# AIRZAI_NFC_READER_FLEX.net
KiCad netlist of a schematic drawn in Altium Designer
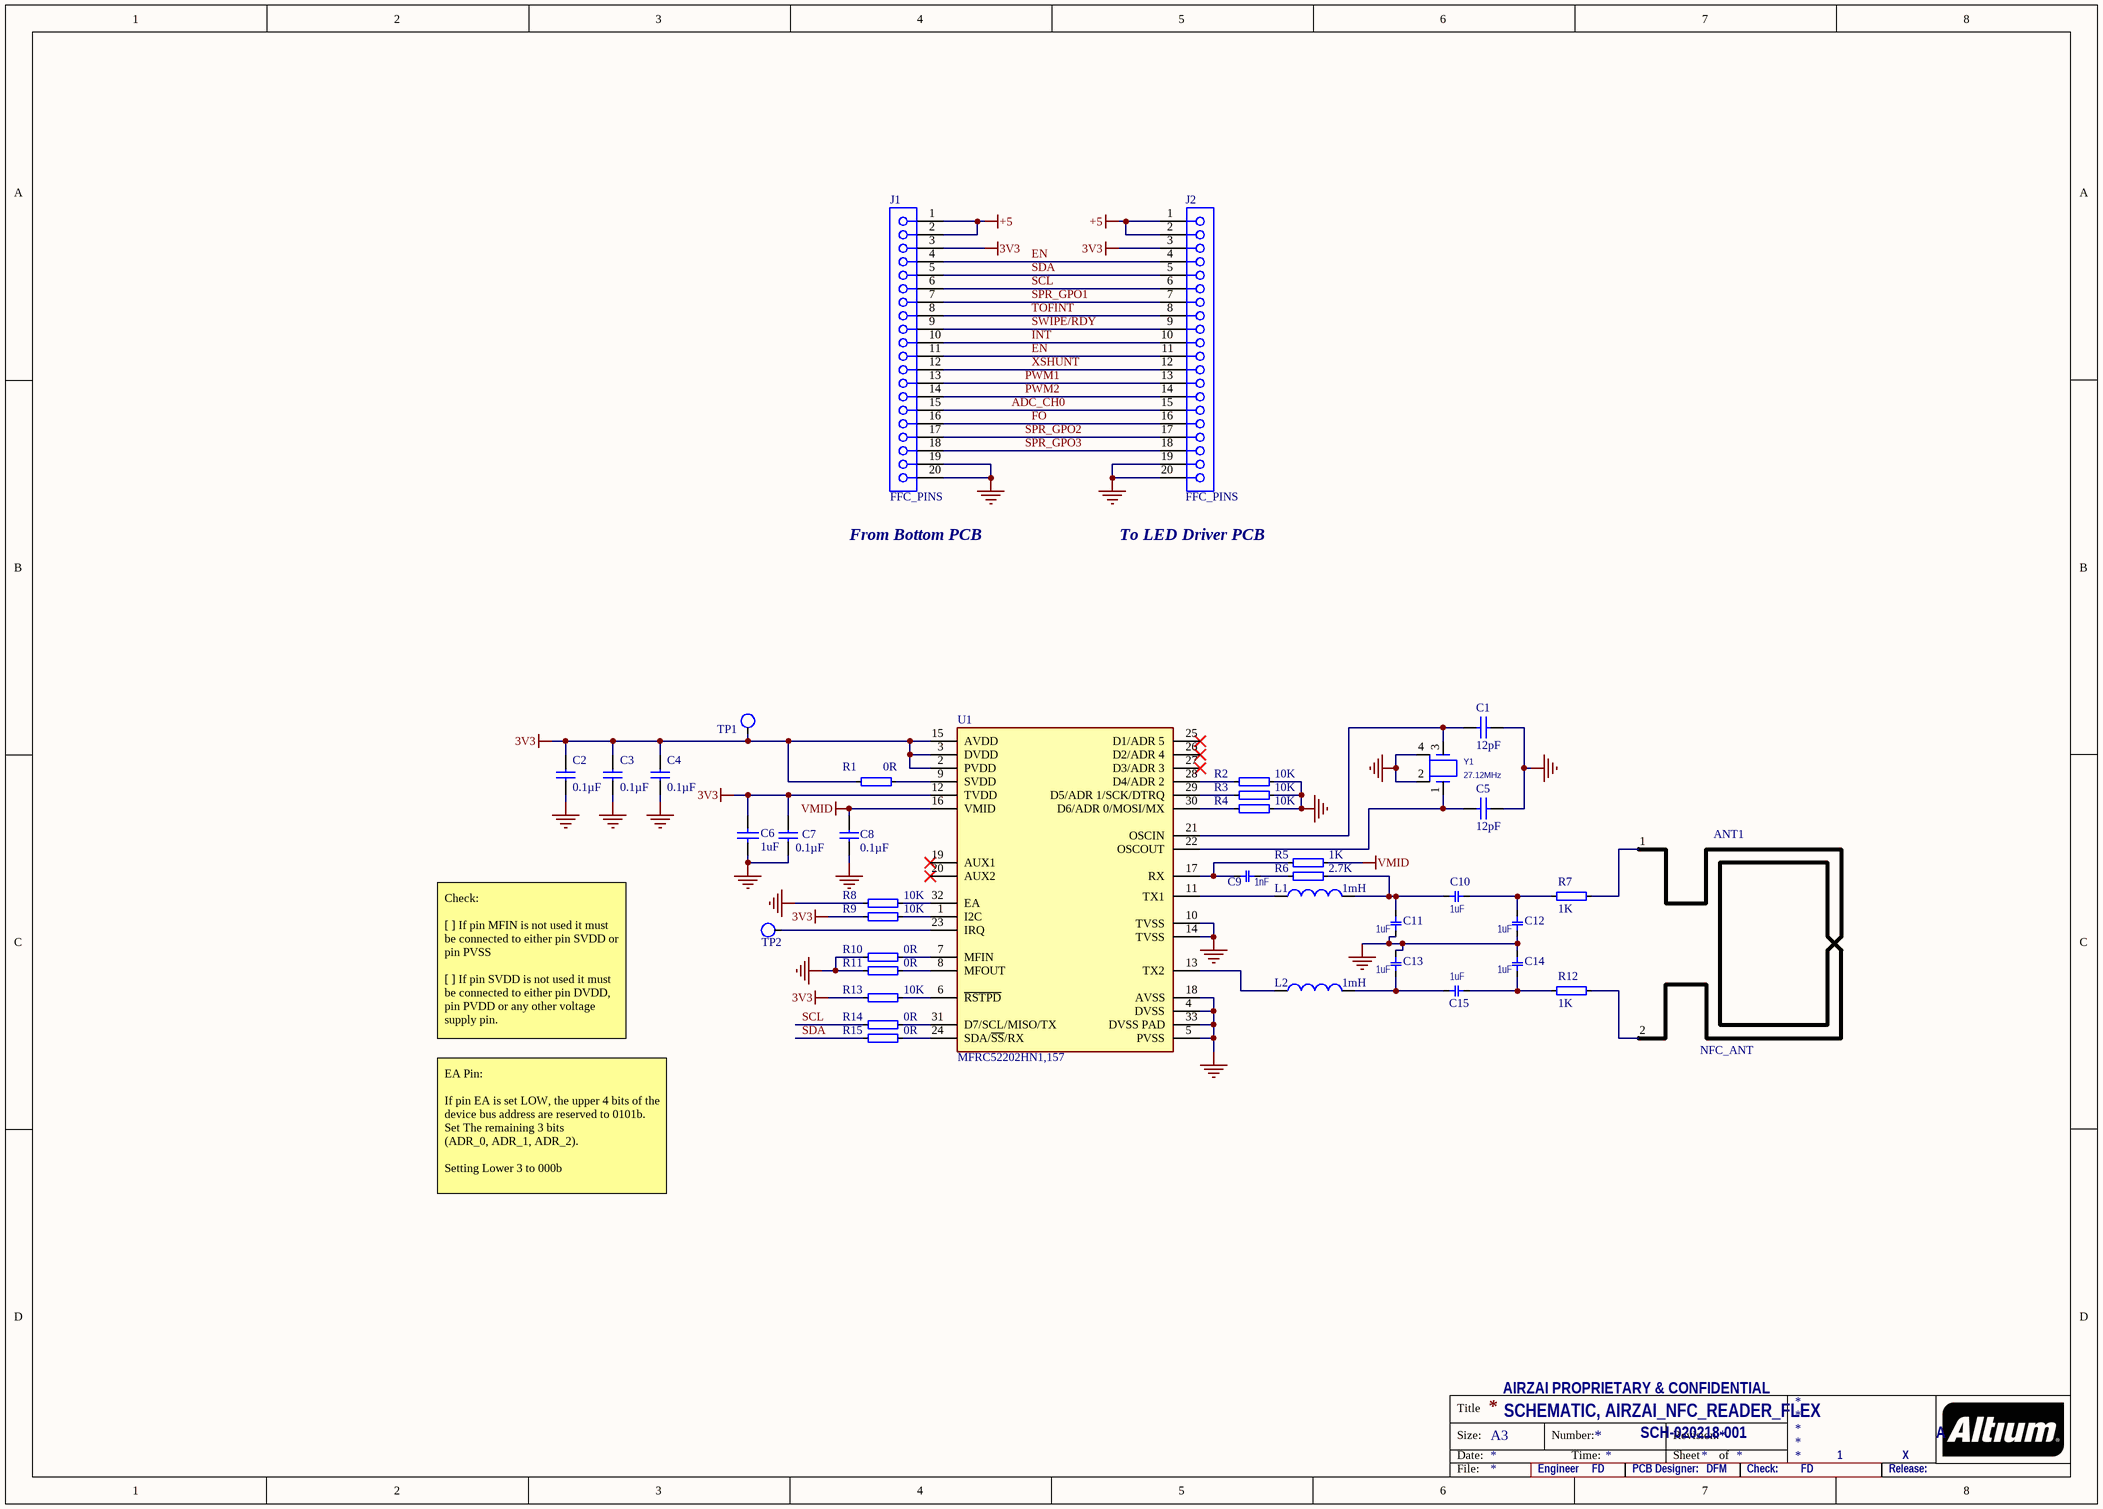
[diagram p0: AIRZAI_NFC_READER_FLEX.SchDoc]

(export (version "E")
  (design (tool "Eeschema 10.0.6"))
  (components
    (comp (ref "ANT1") (value "NFC_ANT") (libsource (lib "AIRZAI_LED_SENSE_FLEX_REVA") (part "NFC_ANT")))
    (comp (ref "C1")
      (value "12pF")
      (description "CAP CER 12PF 50V C0G/NP0 0402")
      (fields
        (field (name "MANUFACTURER") "KEMET")
        (field (name "MANUFACTURER PART NUMBER") "C0402C120J5GACTU")
      )
      (libsource (lib "AIRZAI_LED_SENSE_FLEX_REVA") (part "CAP"))
    )
    (comp (ref "C2")
      (value "0.1µF")
      (footprint "0402CAP")
      (description "Capacitor, X7R, ±10%")
      (fields (field (name "MANUFACTURER") "TDK") (field (name "MANUFACTURER PART NUMBER") "C1005X7R1C104K"))
      (libsource (lib "Nordic Passive DB") (part "CAP"))
    )
    (comp (ref "C3")
      (value "0.1µF")
      (footprint "0402CAP")
      (description "Capacitor, X7R, ±10%")
      (fields (field (name "MANUFACTURER") "TDK") (field (name "MANUFACTURER PART NUMBER") "C1005X7R1C104K"))
      (libsource (lib "Nordic Passive DB") (part "CAP"))
    )
    (comp (ref "C4")
      (value "0.1µF")
      (footprint "0402CAP")
      (description "Capacitor, X7R, ±10%")
      (fields (field (name "MANUFACTURER") "TDK") (field (name "MANUFACTURER PART NUMBER") "C1005X7R1C104K"))
      (libsource (lib "Nordic Passive DB") (part "CAP"))
    )
    (comp (ref "C5")
      (value "12pF")
      (description "CAP CER 12PF 50V C0G/NP0 0402")
      (fields
        (field (name "MANUFACTURER") "KEMET")
        (field (name "MANUFACTURER PART NUMBER") "C0402C120J5GACTU")
      )
      (libsource (lib "AIRZAI_LED_SENSE_FLEX_REVA") (part "CAP"))
    )
    (comp (ref "C6")
      (value "1uF")
      (footprint "CAPC0402(1005)60_M")
      (description "CAP 1uF 16V ±10% 0402 (1005 Metric) Thickness 0.6mm SMD")
      (fields
        (field (name "MANUFACTURER") "Taiyo Yuden")
        (field (name "MANUFACTURER PART NUMBER") "EMK105BJ105KV-F")
      )
      (libsource (lib "AIRZAI_LED_SENSE_FLEX_REVA") (part "CAP"))
    )
    (comp (ref "C7")
      (value "0.1µF")
      (footprint "0402CAP")
      (description "Capacitor, X7R, ±10%")
      (fields (field (name "MANUFACTURER") "TDK") (field (name "MANUFACTURER PART NUMBER") "C1005X7R1C104K"))
      (libsource (lib "Nordic Passive DB") (part "CAP"))
    )
    (comp (ref "C8")
      (value "0.1µF")
      (footprint "0402CAP")
      (description "Capacitor, X7R, ±10%")
      (fields (field (name "MANUFACTURER") "TDK") (field (name "MANUFACTURER PART NUMBER") "C1005X7R1C104K"))
      (libsource (lib "Nordic Passive DB") (part "CAP"))
    )
    (comp (ref "C9") (value "1nF") (footprint "0603") (libsource (lib "LID2131_PN7462AU V2") (part "56p")))
    (comp (ref "C10") (value "1uF") (footprint "0603") (libsource (lib "LID2131_PN7462AU V2") (part "56p")))
    (comp (ref "C11") (value "1uF") (footprint "0603") (libsource (lib "LID2131_PN7462AU V2") (part "56p")))
    (comp (ref "C12") (value "1uF") (footprint "0603") (libsource (lib "LID2131_PN7462AU V2") (part "56p")))
    (comp (ref "C13") (value "1uF") (footprint "0603") (libsource (lib "LID2131_PN7462AU V2") (part "56p")))
    (comp (ref "C14") (value "1uF") (footprint "0603") (libsource (lib "LID2131_PN7462AU V2") (part "56p")))
    (comp (ref "C15") (value "1uF") (footprint "0603") (libsource (lib "LID2131_PN7462AU V2") (part "56p")))
    (comp (ref "J1") (value "FFC_PINS") (libsource (lib "AIRZAI_LED_SENSE_FLEX_REVA") (part "FFC_PINS")))
    (comp (ref "J2") (value "FFC_PINS") (libsource (lib "AIRZAI_LED_SENSE_FLEX_REVA") (part "FFC_PINS")))
    (comp (ref "L1")
      (value "1mH")
      (footprint "0402-A")
      (description "Inductor")
      (libsource (lib "Miscellaneous Devices") (part "Inductor"))
    )
    (comp (ref "L2")
      (value "1mH")
      (footprint "0402-A")
      (description "Inductor")
      (libsource (lib "Miscellaneous Devices") (part "Inductor"))
    )
    (comp (ref "R1")
      (value "0R")
      (footprint "0402")
      (description "Resistor, ±1%, 0.063W")
      (fields
        (field (name "MANUFACTURER") "Panasonic")
        (field (name "MANUFACTURER PART NUMBER") "ERJ-2GE0R00X")
      )
      (libsource (lib "Nordic Passive DB") (part "RES_1"))
    )
    (comp (ref "R2")
      (value "10K")
      (footprint "0402")
      (description "Resistor 10K, ±1%, 0.063W")
      (fields
        (field (name "MANUFACTURER") "Vishay Dale")
        (field (name "MANUFACTURER PART NUMBER") "CRCW040210K0JNED")
      )
      (libsource (lib "Nordic Passive DB") (part "RES_1"))
    )
    (comp (ref "R3")
      (value "10K")
      (footprint "0402")
      (description "Resistor 10K, ±1%, 0.063W")
      (fields
        (field (name "MANUFACTURER") "Vishay Dale")
        (field (name "MANUFACTURER PART NUMBER") "CRCW040210K0JNED")
      )
      (libsource (lib "Nordic Passive DB") (part "RES_1"))
    )
    (comp (ref "R4")
      (value "10K")
      (footprint "0402")
      (description "Resistor 10K, ±1%, 0.063W")
      (fields
        (field (name "MANUFACTURER") "Vishay Dale")
        (field (name "MANUFACTURER PART NUMBER") "CRCW040210K0JNED")
      )
      (libsource (lib "Nordic Passive DB") (part "RES_1"))
    )
    (comp (ref "R5")
      (value "1K")
      (footprint "0402")
      (description "Resistor 1K, ±1%, 0.063W")
      (libsource (lib "Nordic Passive DB") (part "RES_1"))
    )
    (comp (ref "R6")
      (value "2.7K")
      (footprint "0402")
      (description "Resistor 2.7K, ±1%, 0.063W")
      (libsource (lib "Nordic Passive DB") (part "RES_1"))
    )
    (comp (ref "R7")
      (value "1K")
      (description "Resistor 1K, ±1%, 0.063W")
      (libsource (lib "Nordic Passive DB") (part "RES_1"))
    )
    (comp (ref "R8")
      (value "10K")
      (footprint "0402")
      (description "Resistor 10K, ±1%, 0.063W")
      (fields
        (field (name "MANUFACTURER") "Vishay Dale")
        (field (name "MANUFACTURER PART NUMBER") "CRCW040210K0JNED")
      )
      (libsource (lib "Nordic Passive DB") (part "RES_1"))
    )
    (comp (ref "R9")
      (value "10K")
      (footprint "0402")
      (description "Resistor 10K, ±1%, 0.063W")
      (fields
        (field (name "MANUFACTURER") "Vishay Dale")
        (field (name "MANUFACTURER PART NUMBER") "CRCW040210K0JNED")
      )
      (libsource (lib "Nordic Passive DB") (part "RES_1"))
    )
    (comp (ref "R10")
      (value "0R")
      (footprint "0402")
      (description "Resistor, ±1%, 0.063W")
      (fields
        (field (name "MANUFACTURER") "Panasonic")
        (field (name "MANUFACTURER PART NUMBER") "ERJ-2GE0R00X")
      )
      (libsource (lib "Nordic Passive DB") (part "RES_1"))
    )
    (comp (ref "R11")
      (value "0R")
      (footprint "0402")
      (description "Resistor, ±1%, 0.063W")
      (fields
        (field (name "MANUFACTURER") "Panasonic")
        (field (name "MANUFACTURER PART NUMBER") "ERJ-2GE0R00X")
      )
      (libsource (lib "Nordic Passive DB") (part "RES_1"))
    )
    (comp (ref "R12")
      (value "1K")
      (description "Resistor 1K, ±1%, 0.063W")
      (libsource (lib "Nordic Passive DB") (part "RES_1"))
    )
    (comp (ref "R13")
      (value "10K")
      (footprint "0402")
      (description "Resistor 10K, ±1%, 0.063W")
      (fields
        (field (name "MANUFACTURER") "Vishay Dale")
        (field (name "MANUFACTURER PART NUMBER") "CRCW040210K0JNED")
      )
      (libsource (lib "Nordic Passive DB") (part "RES_1"))
    )
    (comp (ref "R14")
      (value "0R")
      (footprint "0402")
      (description "Resistor, ±1%, 0.063W")
      (fields
        (field (name "MANUFACTURER") "Panasonic")
        (field (name "MANUFACTURER PART NUMBER") "ERJ-2GE0R00X")
      )
      (libsource (lib "Nordic Passive DB") (part "RES_1"))
    )
    (comp (ref "R15")
      (value "0R")
      (footprint "0402")
      (description "Resistor, ±1%, 0.063W")
      (fields
        (field (name "MANUFACTURER") "Panasonic")
        (field (name "MANUFACTURER PART NUMBER") "ERJ-2GE0R00X")
      )
      (libsource (lib "Nordic Passive DB") (part "RES_1"))
    )
    (comp (ref "TP1")
      (value "WIREPT")
      (footprint "TP_0.9MM")
      (libsource (lib "AIRZAI_MBD_REVB") (part "WIREPT"))
    )
    (comp (ref "TP2")
      (value "WIREPT")
      (footprint "TP_0.9MM")
      (libsource (lib "AIRZAI_MBD_REVB") (part "WIREPT"))
    )
    (comp (ref "U1")
      (value "MFRC52201HN1,157")
      (footprint "NXP_SOT617-1_0")
      (description "IC RFID READER 13.56MHZ 32HVQFN")
      (fields
        (field (name "MANUFACTURER") "NXP")
        (field (name "MOUSER PART NUMBER") "771-MFRC52202HN1157")
        (field (name "PART NUMBER") "MFRC52202HN1,157")
      )
      (libsource (lib "AIRZAI_LED_SENSE_FLEX_REVA") (part "MFRC52201HN1,157"))
    )
    (comp (ref "Y1")
      (value "27.12MHz")
      (footprint "XTAL_2016")
      (description "CRYSTAL 27.12MHZ 10PF SMD")
      (fields
        (field (name "MANUFACTURER") "ECS International")
        (field (name "MANUFACTURER PART NUMBER") "ECS-271.2-10-37-CKM-TR")
      )
      (libsource (lib "*") (part "ZTB_2"))
    )
  )
  (nets
    (net (code "1") (name "+5") (class "Default")
      (node (ref "J1") (pin "1") (pinfunction "1_1") (pintype "passive"))
      (node (ref "J1") (pin "2") (pinfunction "2_2") (pintype "passive"))
      (node (ref "J2") (pin "1") (pinfunction "1_1") (pintype "passive"))
      (node (ref "J2") (pin "2") (pinfunction "2_2") (pintype "passive"))
    )
    (net (code "2") (name "/ADC_CH0") (class "Default")
      (node (ref "J1") (pin "15") (pinfunction "15_15") (pintype "passive"))
      (node (ref "J2") (pin "15") (pinfunction "15_15") (pintype "passive"))
    )
    (net (code "3") (name "/EN") (class "Default")
      (node (ref "J1") (pin "11") (pinfunction "11_11") (pintype "passive"))
      (node (ref "J1") (pin "4") (pinfunction "4_4") (pintype "passive"))
      (node (ref "J2") (pin "11") (pinfunction "11_11") (pintype "passive"))
      (node (ref "J2") (pin "4") (pinfunction "4_4") (pintype "passive"))
    )
    (net (code "4") (name "/FO") (class "Default")
      (node (ref "J1") (pin "16") (pinfunction "16_16") (pintype "passive"))
      (node (ref "J2") (pin "16") (pinfunction "16_16") (pintype "passive"))
    )
    (net (code "5") (name "/INT") (class "Default")
      (node (ref "J1") (pin "10") (pinfunction "10_10") (pintype "passive"))
      (node (ref "J2") (pin "10") (pinfunction "10_10") (pintype "passive"))
    )
    (net (code "6") (name "/PWM1") (class "Default")
      (node (ref "J1") (pin "13") (pinfunction "13_13") (pintype "passive"))
      (node (ref "J2") (pin "13") (pinfunction "13_13") (pintype "passive"))
    )
    (net (code "7") (name "/PWM2") (class "Default")
      (node (ref "J1") (pin "14") (pinfunction "14_14") (pintype "passive"))
      (node (ref "J2") (pin "14") (pinfunction "14_14") (pintype "passive"))
    )
    (net (code "8") (name "/SCL") (class "Default")
      (node (ref "J1") (pin "6") (pinfunction "6_6") (pintype "passive"))
      (node (ref "J2") (pin "6") (pinfunction "6_6") (pintype "passive"))
      (node (ref "R14") (pin "2") (pinfunction "2_2") (pintype "passive"))
    )
    (net (code "9") (name "/SDA") (class "Default")
      (node (ref "J1") (pin "5") (pinfunction "5_5") (pintype "passive"))
      (node (ref "J2") (pin "5") (pinfunction "5_5") (pintype "passive"))
      (node (ref "R15") (pin "2") (pinfunction "2_2") (pintype "passive"))
    )
    (net (code "10") (name "/SPR_GPO1") (class "Default")
      (node (ref "J1") (pin "7") (pinfunction "7_7") (pintype "passive"))
      (node (ref "J2") (pin "7") (pinfunction "7_7") (pintype "passive"))
    )
    (net (code "11") (name "/SPR_GPO2") (class "Default")
      (node (ref "J1") (pin "17") (pinfunction "17_17") (pintype "passive"))
      (node (ref "J2") (pin "17") (pinfunction "17_17") (pintype "passive"))
    )
    (net (code "12") (name "/SPR_GPO3") (class "Default")
      (node (ref "J1") (pin "18") (pinfunction "18_18") (pintype "passive"))
      (node (ref "J2") (pin "18") (pinfunction "18_18") (pintype "passive"))
    )
    (net (code "13") (name "/SWIPE{slash}RDY") (class "Default")
      (node (ref "J1") (pin "9") (pinfunction "9_9") (pintype "passive"))
      (node (ref "J2") (pin "9") (pinfunction "9_9") (pintype "passive"))
    )
    (net (code "14") (name "/TOFINT") (class "Default")
      (node (ref "J1") (pin "8") (pinfunction "8_8") (pintype "passive"))
      (node (ref "J2") (pin "8") (pinfunction "8_8") (pintype "passive"))
    )
    (net (code "15") (name "/XSHUNT") (class "Default")
      (node (ref "J1") (pin "12") (pinfunction "12_12") (pintype "passive"))
      (node (ref "J2") (pin "12") (pinfunction "12_12") (pintype "passive"))
    )
    (net (code "16") (name "3V3") (class "Default")
      (node (ref "C2") (pin "1") (pinfunction "1_1") (pintype "passive"))
      (node (ref "C3") (pin "1") (pinfunction "1_1") (pintype "passive"))
      (node (ref "C4") (pin "1") (pinfunction "1_1") (pintype "passive"))
      (node (ref "C6") (pin "2") (pinfunction "2_2") (pintype "passive"))
      (node (ref "C7") (pin "1") (pinfunction "1_1") (pintype "passive"))
      (node (ref "J1") (pin "3") (pinfunction "3_3") (pintype "passive"))
      (node (ref "J2") (pin "3") (pinfunction "3_3") (pintype "passive"))
      (node (ref "R1") (pin "2") (pinfunction "2_2") (pintype "passive"))
      (node (ref "R13") (pin "2") (pinfunction "2_2") (pintype "passive"))
      (node (ref "R9") (pin "2") (pinfunction "2_2") (pintype "passive"))
      (node (ref "TP1") (pin "1") (pinfunction "1_1") (pintype "passive"))
      (node (ref "U1") (pin "12") (pinfunction "TVDD_12") (pintype "passive"))
      (node (ref "U1") (pin "15") (pinfunction "AVDD_15") (pintype "passive"))
      (node (ref "U1") (pin "2") (pinfunction "PVDD_2") (pintype "passive"))
      (node (ref "U1") (pin "3") (pinfunction "DVDD_3") (pintype "passive"))
    )
    (net (code "17") (name "GND") (class "Default")
      (node (ref "C1") (pin "1") (pinfunction "1_1") (pintype "passive"))
      (node (ref "C11") (pin "1") (pinfunction "1_1") (pintype "passive"))
      (node (ref "C12") (pin "1") (pinfunction "1_1") (pintype "passive"))
      (node (ref "C13") (pin "2") (pinfunction "2_2") (pintype "passive"))
      (node (ref "C14") (pin "2") (pinfunction "2_2") (pintype "passive"))
      (node (ref "C2") (pin "2") (pinfunction "2_2") (pintype "passive"))
      (node (ref "C3") (pin "2") (pinfunction "2_2") (pintype "passive"))
      (node (ref "C4") (pin "2") (pinfunction "2_2") (pintype "passive"))
      (node (ref "C5") (pin "1") (pinfunction "1_1") (pintype "passive"))
      (node (ref "C6") (pin "1") (pinfunction "1_1") (pintype "passive"))
      (node (ref "C7") (pin "2") (pinfunction "2_2") (pintype "passive"))
      (node (ref "C8") (pin "2") (pinfunction "2_2") (pintype "passive"))
      (node (ref "J1") (pin "19") (pinfunction "19_19") (pintype "passive"))
      (node (ref "J1") (pin "20") (pinfunction "20_20") (pintype "passive"))
      (node (ref "J2") (pin "19") (pinfunction "19_19") (pintype "passive"))
      (node (ref "J2") (pin "20") (pinfunction "20_20") (pintype "passive"))
      (node (ref "R10") (pin "2") (pinfunction "2_2") (pintype "passive"))
      (node (ref "R11") (pin "2") (pinfunction "2_2") (pintype "passive"))
      (node (ref "R2") (pin "1") (pinfunction "1_1") (pintype "passive"))
      (node (ref "R3") (pin "1") (pinfunction "1_1") (pintype "passive"))
      (node (ref "R4") (pin "1") (pinfunction "1_1") (pintype "passive"))
      (node (ref "R8") (pin "2") (pinfunction "2_2") (pintype "passive"))
      (node (ref "U1") (pin "10") (pinfunction "TVSS_10") (pintype "passive"))
      (node (ref "U1") (pin "14") (pinfunction "TVSS_14") (pintype "passive"))
      (node (ref "U1") (pin "18") (pinfunction "AVSS_18") (pintype "passive"))
      (node (ref "U1") (pin "33") (pinfunction "DVSS_PAD_33") (pintype "passive"))
      (node (ref "U1") (pin "4") (pinfunction "DVSS_4") (pintype "passive"))
      (node (ref "U1") (pin "5") (pinfunction "PVSS_5") (pintype "passive"))
      (node (ref "Y1") (pin "2") (pinfunction "2_2") (pintype "passive"))
      (node (ref "Y1") (pin "4") (pinfunction "4_4") (pintype "passive"))
    )
    (net (code "18") (name "Net-(ANT1-Pad1)") (class "Default")
      (node (ref "ANT1") (pin "1") (pinfunction "1_1") (pintype "passive"))
      (node (ref "R7") (pin "1") (pinfunction "1_1") (pintype "passive"))
    )
    (net (code "19") (name "Net-(ANT1-Pad2)") (class "Default")
      (node (ref "ANT1") (pin "2") (pinfunction "2_2") (pintype "passive"))
      (node (ref "R12") (pin "1") (pinfunction "1_1") (pintype "passive"))
    )
    (net (code "20") (name "Net-(C9-Pad1)") (class "Default")
      (node (ref "C9") (pin "1") (pinfunction "1_1") (pintype "passive"))
      (node (ref "R6") (pin "2") (pinfunction "2_2") (pintype "passive"))
    )
    (net (code "21") (name "Net-(C10-Pad1)") (class "Default")
      (node (ref "C10") (pin "1") (pinfunction "1_1") (pintype "passive"))
      (node (ref "C12") (pin "2") (pinfunction "2_2") (pintype "passive"))
      (node (ref "R7") (pin "2") (pinfunction "2_2") (pintype "passive"))
    )
    (net (code "22") (name "Net-(C10-Pad2)") (class "Default")
      (node (ref "C10") (pin "2") (pinfunction "2_2") (pintype "passive"))
      (node (ref "C11") (pin "2") (pinfunction "2_2") (pintype "passive"))
      (node (ref "L1") (pin "2") (pinfunction "2_2") (pintype "passive"))
      (node (ref "R6") (pin "1") (pinfunction "1_1") (pintype "passive"))
    )
    (net (code "23") (name "Net-(C13-Pad1)") (class "Default")
      (node (ref "C13") (pin "1") (pinfunction "1_1") (pintype "passive"))
      (node (ref "C15") (pin "2") (pinfunction "2_2") (pintype "passive"))
      (node (ref "L2") (pin "2") (pinfunction "2_2") (pintype "passive"))
    )
    (net (code "24") (name "Net-(C14-Pad1)") (class "Default")
      (node (ref "C14") (pin "1") (pinfunction "1_1") (pintype "passive"))
      (node (ref "C15") (pin "1") (pinfunction "1_1") (pintype "passive"))
      (node (ref "R12") (pin "2") (pinfunction "2_2") (pintype "passive"))
    )
    (net (code "25") (name "Net-(U1-D4{slash}ADR_2)") (class "Default")
      (node (ref "R2") (pin "2") (pinfunction "2_2") (pintype "passive"))
      (node (ref "U1") (pin "28") (pinfunction "D4/ADR_2_28") (pintype "passive"))
    )
    (net (code "26") (name "Net-(U1-D5{slash}ADR_1{slash}SCK{slash}DTRQ)") (class "Default")
      (node (ref "R3") (pin "2") (pinfunction "2_2") (pintype "passive"))
      (node (ref "U1") (pin "29") (pinfunction "D5/ADR_1/SCK/DTRQ_29") (pintype "passive"))
    )
    (net (code "27") (name "Net-(U1-D6{slash}ADR_0{slash}MOSI{slash}MX)") (class "Default")
      (node (ref "R4") (pin "2") (pinfunction "2_2") (pintype "passive"))
      (node (ref "U1") (pin "30") (pinfunction "D6/ADR_0/MOSI/MX_30") (pintype "passive"))
    )
    (net (code "28") (name "Net-(U1-D7{slash}SCL{slash}MISO{slash}TX)") (class "Default")
      (node (ref "R14") (pin "1") (pinfunction "1_1") (pintype "passive"))
      (node (ref "U1") (pin "31") (pinfunction "D7/SCL/MISO/TX_31") (pintype "passive"))
    )
    (net (code "29") (name "Net-(U1-EA)") (class "Default")
      (node (ref "R8") (pin "1") (pinfunction "1_1") (pintype "passive"))
      (node (ref "U1") (pin "32") (pinfunction "EA_32") (pintype "passive"))
    )
    (net (code "30") (name "Net-(U1-I2C)") (class "Default")
      (node (ref "R9") (pin "1") (pinfunction "1_1") (pintype "passive"))
      (node (ref "U1") (pin "1") (pinfunction "I2C_1") (pintype "passive"))
    )
    (net (code "31") (name "Net-(U1-IRQ)") (class "Default")
      (node (ref "TP2") (pin "1") (pinfunction "1_1") (pintype "passive"))
      (node (ref "U1") (pin "23") (pinfunction "IRQ_23") (pintype "passive"))
    )
    (net (code "32") (name "Net-(U1-MFIN)") (class "Default")
      (node (ref "R10") (pin "1") (pinfunction "1_1") (pintype "passive"))
      (node (ref "U1") (pin "7") (pinfunction "MFIN_7") (pintype "passive"))
    )
    (net (code "33") (name "Net-(U1-MFOUT)") (class "Default")
      (node (ref "R11") (pin "1") (pinfunction "1_1") (pintype "passive"))
      (node (ref "U1") (pin "8") (pinfunction "MFOUT_8") (pintype "passive"))
    )
    (net (code "34") (name "Net-(U1-OSCIN)") (class "Default")
      (node (ref "C1") (pin "2") (pinfunction "2_2") (pintype "passive"))
      (node (ref "U1") (pin "21") (pinfunction "OSCIN_21") (pintype "passive"))
      (node (ref "Y1") (pin "3") (pinfunction "3_3") (pintype "passive"))
    )
    (net (code "35") (name "Net-(U1-OSCOUT)") (class "Default")
      (node (ref "C5") (pin "2") (pinfunction "2_2") (pintype "passive"))
      (node (ref "U1") (pin "22") (pinfunction "OSCOUT_22") (pintype "passive"))
      (node (ref "Y1") (pin "1") (pinfunction "1_1") (pintype "passive"))
    )
    (net (code "36") (name "Net-(U1-RX)") (class "Default")
      (node (ref "C9") (pin "2") (pinfunction "2_2") (pintype "passive"))
      (node (ref "R5") (pin "2") (pinfunction "2_2") (pintype "passive"))
      (node (ref "U1") (pin "17") (pinfunction "RX_17") (pintype "passive"))
    )
    (net (code "37") (name "Net-(U1-SDA{slash}~{SS}{slash}RX)") (class "Default")
      (node (ref "R15") (pin "1") (pinfunction "1_1") (pintype "passive"))
      (node (ref "U1") (pin "24") (pinfunction "SDA/~{SS}/RX_24") (pintype "passive"))
    )
    (net (code "38") (name "Net-(U1-SVDD)") (class "Default")
      (node (ref "R1") (pin "1") (pinfunction "1_1") (pintype "passive"))
      (node (ref "U1") (pin "9") (pinfunction "SVDD_9") (pintype "passive"))
    )
    (net (code "39") (name "Net-(U1-TX1)") (class "Default")
      (node (ref "L1") (pin "1") (pinfunction "1_1") (pintype "passive"))
      (node (ref "U1") (pin "11") (pinfunction "TX1_11") (pintype "passive"))
    )
    (net (code "40") (name "Net-(U1-TX2)") (class "Default")
      (node (ref "L2") (pin "1") (pinfunction "1_1") (pintype "passive"))
      (node (ref "U1") (pin "13") (pinfunction "TX2_13") (pintype "passive"))
    )
    (net (code "41") (name "Net-(U1-~{RSTPD})") (class "Default")
      (node (ref "R13") (pin "1") (pinfunction "1_1") (pintype "passive"))
      (node (ref "U1") (pin "6") (pinfunction "~{RSTPD}_6") (pintype "passive"))
    )
    (net (code "42") (name "VMID") (class "Default")
      (node (ref "C8") (pin "1") (pinfunction "1_1") (pintype "passive"))
      (node (ref "R5") (pin "1") (pinfunction "1_1") (pintype "passive"))
      (node (ref "U1") (pin "16") (pinfunction "VMID_16") (pintype "passive"))
    )
    (net (code "43") (name "unconnected-(U1-AUX1-Pad19)") (class "Default")
      (node (ref "U1") (pin "19") (pinfunction "AUX1_19") (pintype "passive+no_connect"))
    )
    (net (code "44") (name "unconnected-(U1-AUX2-Pad20)") (class "Default")
      (node (ref "U1") (pin "20") (pinfunction "AUX2_20") (pintype "passive+no_connect"))
    )
    (net (code "45") (name "unconnected-(U1-D1{slash}ADR_5-Pad25)") (class "Default")
      (node (ref "U1") (pin "25") (pinfunction "D1/ADR_5_25") (pintype "passive+no_connect"))
    )
    (net (code "46") (name "unconnected-(U1-D2{slash}ADR_4-Pad26)") (class "Default")
      (node (ref "U1") (pin "26") (pinfunction "D2/ADR_4_26") (pintype "passive+no_connect"))
    )
    (net (code "47") (name "unconnected-(U1-D3{slash}ADR_3-Pad27)") (class "Default")
      (node (ref "U1") (pin "27") (pinfunction "D3/ADR_3_27") (pintype "passive+no_connect"))
    )
  )
)
